# 1-cell-mcu.net
KiCad netlist of a schematic drawn in EAGLE
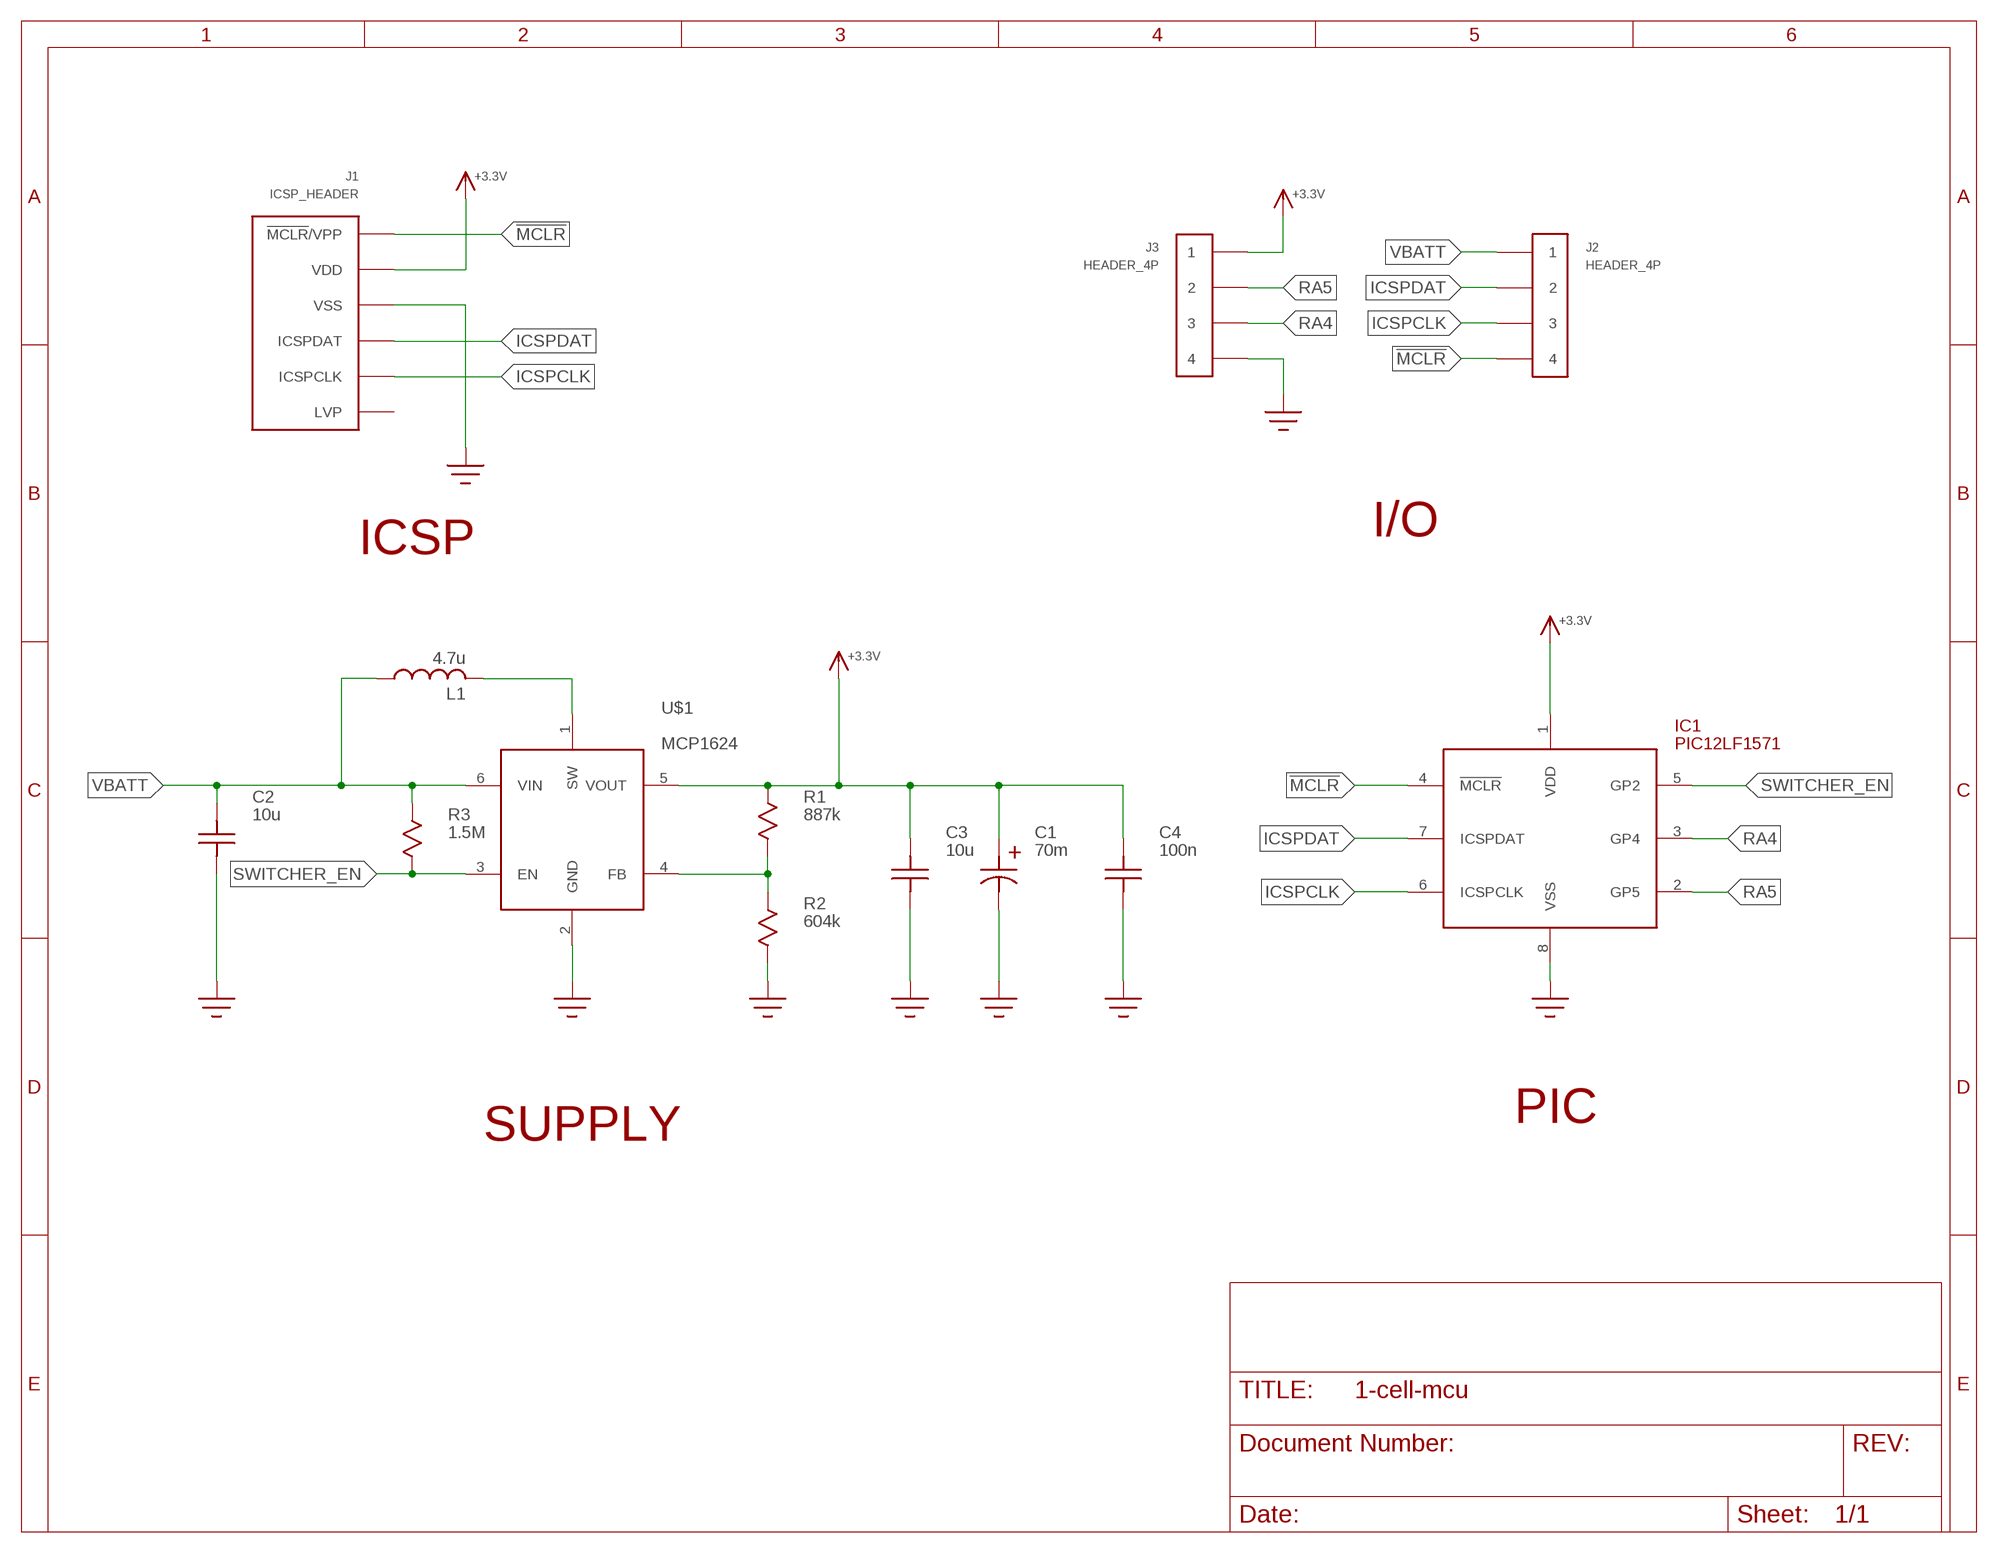
[diagram p0: schematic, sheet 1]

(export (version "E")
  (design (tool "Eeschema 10.0.6"))
  (components
    (comp (ref "C1")
      (value "70m")
      (footprint "eagle-import:ELNA_HL_SUPERCAP")
      (libsource (lib "eagle-import") (part "C_POL"))
    )
    (comp (ref "C2")
      (value "10u")
      (footprint "eagle-import:1206")
      (libsource (lib "eagle-import") (part "C1206"))
    )
    (comp (ref "C3")
      (value "10u")
      (footprint "eagle-import:1206")
      (libsource (lib "eagle-import") (part "C1206"))
    )
    (comp (ref "C4")
      (value "100n")
      (footprint "eagle-import:0805")
      (libsource (lib "eagle-import") (part "C0805"))
    )
    (comp (ref "IC1")
      (value "PIC12LF1571")
      (footprint "eagle-import:SOIC8")
      (libsource (lib "eagle-import") (part "PIC12LF1571"))
    )
    (comp (ref "J1")
      (value "ICSP_HEADER")
      (footprint "eagle-import:HEADER_6P")
      (libsource (lib "eagle-import") (part "ICSP_HEADER"))
    )
    (comp (ref "J2")
      (value "HEADER_4P")
      (footprint "eagle-import:HEADER_4P")
      (libsource (lib "eagle-import") (part "HEADER_4P"))
    )
    (comp (ref "J3")
      (value "HEADER_4P")
      (footprint "eagle-import:HEADER_4P")
      (libsource (lib "eagle-import") (part "HEADER_4P"))
    )
    (comp (ref "L1")
      (value "4.7u")
      (footprint "eagle-import:4040_INDUCTOR")
      (libsource (lib "eagle-import") (part "INDUCTOR4040"))
    )
    (comp (ref "R1")
      (value "887k")
      (footprint "eagle-import:R0805")
      (libsource (lib "eagle-import") (part "R0805"))
    )
    (comp (ref "R2")
      (value "604k")
      (footprint "eagle-import:R0805")
      (libsource (lib "eagle-import") (part "R0805"))
    )
    (comp (ref "R3")
      (value "1.5M")
      (footprint "eagle-import:R0805")
      (libsource (lib "eagle-import") (part "R0805"))
    )
    (comp (ref "U$1")
      (value "MCP1624")
      (footprint "eagle-import:SOT23-6")
      (libsource (lib "eagle-import") (part "MCP1624"))
    )
  )
  (nets
    (net (code "1") (name "+3.3V") (class "Default")
      (node (ref "C1") (pin "+") (pinfunction "+_+") (pintype "bidirectional"))
      (node (ref "C3") (pin "P$2") (pinfunction "P$2_P$2") (pintype "bidirectional"))
      (node (ref "C4") (pin "P$2") (pinfunction "P$2_P$2") (pintype "bidirectional"))
      (node (ref "IC1") (pin "1") (pinfunction "VDD_1") (pintype "bidirectional"))
      (node (ref "J1") (pin "2") (pinfunction "VDD_2") (pintype "bidirectional"))
      (node (ref "J3") (pin "1") (pinfunction "1_1") (pintype "bidirectional"))
      (node (ref "R1") (pin "P$1") (pinfunction "P$3_P$1") (pintype "bidirectional"))
      (node (ref "U$1") (pin "5") (pinfunction "VOUT_5") (pintype "bidirectional"))
    )
    (net (code "2") (name "/~{MCLR}") (class "Default")
      (node (ref "IC1") (pin "4") (pinfunction "~{MCLR}_4") (pintype "bidirectional"))
      (node (ref "J1") (pin "1") (pinfunction "~{MCLR}/VPP_1") (pintype "bidirectional"))
      (node (ref "J2") (pin "4") (pinfunction "4_4") (pintype "bidirectional"))
    )
    (net (code "3") (name "GND") (class "Default")
      (node (ref "C1") (pin "-") (pinfunction "-_-") (pintype "bidirectional"))
      (node (ref "C2") (pin "P$1") (pinfunction "P$1_P$1") (pintype "bidirectional"))
      (node (ref "C3") (pin "P$1") (pinfunction "P$1_P$1") (pintype "bidirectional"))
      (node (ref "C4") (pin "P$1") (pinfunction "P$1_P$1") (pintype "bidirectional"))
      (node (ref "IC1") (pin "8") (pinfunction "VSS_8") (pintype "bidirectional"))
      (node (ref "J1") (pin "3") (pinfunction "VSS_3") (pintype "bidirectional"))
      (node (ref "J3") (pin "4") (pinfunction "4_4") (pintype "bidirectional"))
      (node (ref "R2") (pin "P$2") (pinfunction "P$4_P$2") (pintype "bidirectional"))
      (node (ref "U$1") (pin "2") (pinfunction "GND_2") (pintype "bidirectional"))
    )
    (net (code "4") (name "ICSPCLK") (class "Default")
      (node (ref "IC1") (pin "6") (pinfunction "ICSPCLK_6") (pintype "bidirectional"))
      (node (ref "J1") (pin "5") (pinfunction "ICSPCLK_5") (pintype "bidirectional"))
      (node (ref "J2") (pin "3") (pinfunction "3_3") (pintype "bidirectional"))
    )
    (net (code "5") (name "ICSPDAT") (class "Default")
      (node (ref "IC1") (pin "7") (pinfunction "ICSPDAT_7") (pintype "bidirectional"))
      (node (ref "J1") (pin "4") (pinfunction "ICSPDAT_4") (pintype "bidirectional"))
      (node (ref "J2") (pin "2") (pinfunction "2_2") (pintype "bidirectional"))
    )
    (net (code "6") (name "Net-(L1-2)") (class "Default")
      (node (ref "L1") (pin "P$2") (pinfunction "2_P$2") (pintype "passive"))
      (node (ref "U$1") (pin "1") (pinfunction "SW_1") (pintype "bidirectional"))
    )
    (net (code "7") (name "Net-(R1-P$4)") (class "Default")
      (node (ref "R1") (pin "P$2") (pinfunction "P$4_P$2") (pintype "bidirectional"))
      (node (ref "R2") (pin "P$1") (pinfunction "P$3_P$1") (pintype "bidirectional"))
      (node (ref "U$1") (pin "4") (pinfunction "FB_4") (pintype "bidirectional"))
    )
    (net (code "8") (name "RA4") (class "Default")
      (node (ref "IC1") (pin "3") (pinfunction "GP4_3") (pintype "bidirectional"))
      (node (ref "J3") (pin "3") (pinfunction "3_3") (pintype "bidirectional"))
    )
    (net (code "9") (name "RA5") (class "Default")
      (node (ref "IC1") (pin "2") (pinfunction "GP5_2") (pintype "bidirectional"))
      (node (ref "J3") (pin "2") (pinfunction "2_2") (pintype "bidirectional"))
    )
    (net (code "10") (name "SWITCHER_EN") (class "Default")
      (node (ref "IC1") (pin "5") (pinfunction "GP2_5") (pintype "bidirectional"))
      (node (ref "R3") (pin "P$2") (pinfunction "P$4_P$2") (pintype "bidirectional"))
      (node (ref "U$1") (pin "3") (pinfunction "EN_3") (pintype "bidirectional"))
    )
    (net (code "11") (name "VBATT") (class "Default")
      (node (ref "C2") (pin "P$2") (pinfunction "P$2_P$2") (pintype "bidirectional"))
      (node (ref "J2") (pin "1") (pinfunction "1_1") (pintype "bidirectional"))
      (node (ref "L1") (pin "P$1") (pinfunction "1_P$1") (pintype "passive"))
      (node (ref "R3") (pin "P$1") (pinfunction "P$3_P$1") (pintype "bidirectional"))
      (node (ref "U$1") (pin "6") (pinfunction "VIN_6") (pintype "bidirectional"))
    )
    (net (code "12") (name "unconnected-(J1-LVP-Pad6)") (class "Default")
      (node (ref "J1") (pin "6") (pinfunction "LVP_6") (pintype "bidirectional"))
    )
  )
)
